# Board_roomba_final.net
KiCad netlist of a schematic drawn in EAGLE
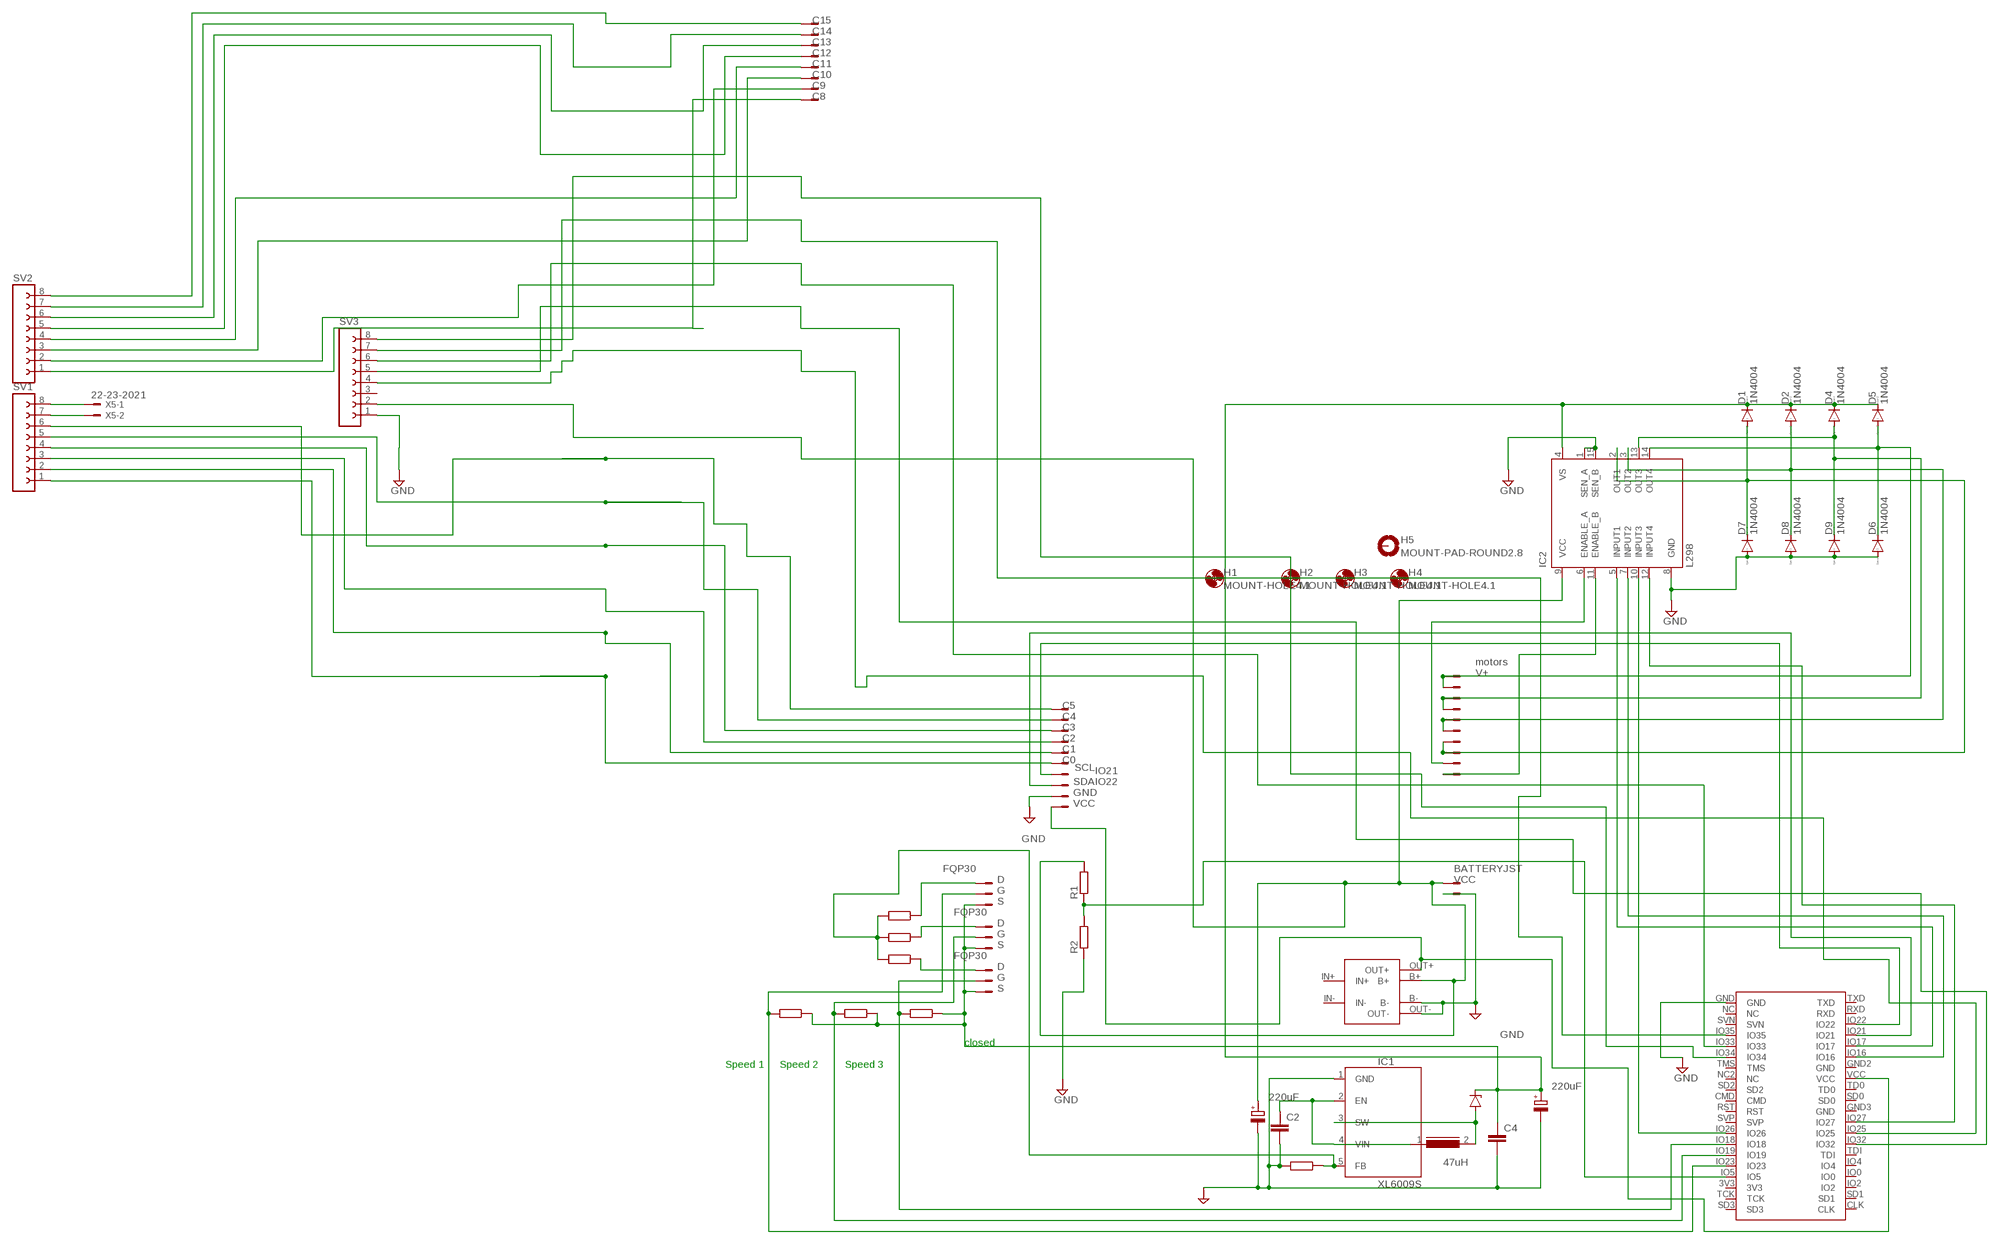
[diagram p0: schematic, sheet 1]

(export (version "E")
  (design (tool "Eeschema 10.0.6"))
  (components
    (comp (ref "C1")
      (value "CPOL-EUE2.5-7")
      (footprint "eagle-import:E2,5-7")
      (fields (field (name "SPICEPREFIX") "C") (field (name "SPICEPREFIX_1") "220uF"))
      (libsource (lib "eagle-import") (part "CPOL-EUE2.5-7"))
    )
    (comp (ref "C2")
      (value "C2,5-3")
      (footprint "eagle-import:C2.5-3")
      (libsource (lib "eagle-import") (part "C2,5-3"))
    )
    (comp (ref "C3")
      (value "CPOL-EUE2.5-7")
      (footprint "eagle-import:E2,5-7")
      (fields (field (name "SPICEPREFIX") "C") (field (name "SPICEPREFIX_1") "220uF"))
      (libsource (lib "eagle-import") (part "CPOL-EUE2.5-7"))
    )
    (comp (ref "C4")
      (value "C2,5-3")
      (footprint "eagle-import:C2.5-3")
      (libsource (lib "eagle-import") (part "C2,5-3"))
    )
    (comp (ref "D1")
      (value "1N4004")
      (footprint "eagle-import:DO41-10")
      (libsource (lib "eagle-import") (part "1N4004"))
    )
    (comp (ref "D2")
      (value "1N4004")
      (footprint "eagle-import:DO41-10")
      (libsource (lib "eagle-import") (part "1N4004"))
    )
    (comp (ref "D3")
      (value "1N4728")
      (footprint "eagle-import:DO41Z10")
      (libsource (lib "eagle-import") (part "1N4728"))
    )
    (comp (ref "D4")
      (value "1N4004")
      (footprint "eagle-import:DO41-10")
      (libsource (lib "eagle-import") (part "1N4004"))
    )
    (comp (ref "D5")
      (value "1N4004")
      (footprint "eagle-import:DO41-10")
      (libsource (lib "eagle-import") (part "1N4004"))
    )
    (comp (ref "D6")
      (value "1N4004")
      (footprint "eagle-import:DO41-10")
      (libsource (lib "eagle-import") (part "1N4004"))
    )
    (comp (ref "D7")
      (value "1N4004")
      (footprint "eagle-import:DO41-10")
      (libsource (lib "eagle-import") (part "1N4004"))
    )
    (comp (ref "D8")
      (value "1N4004")
      (footprint "eagle-import:DO41-10")
      (libsource (lib "eagle-import") (part "1N4004"))
    )
    (comp (ref "D9")
      (value "1N4004")
      (footprint "eagle-import:DO41-10")
      (libsource (lib "eagle-import") (part "1N4004"))
    )
    (comp (ref "H1")
      (value "MOUNT-HOLE4.1")
      (footprint "eagle-import:4,1")
      (libsource (lib "eagle-import") (part "MOUNT-HOLE4.1"))
    )
    (comp (ref "H2")
      (value "MOUNT-HOLE4.1")
      (footprint "eagle-import:4,1")
      (libsource (lib "eagle-import") (part "MOUNT-HOLE4.1"))
    )
    (comp (ref "H3")
      (value "MOUNT-HOLE4.1")
      (footprint "eagle-import:4,1")
      (libsource (lib "eagle-import") (part "MOUNT-HOLE4.1"))
    )
    (comp (ref "H4")
      (value "MOUNT-HOLE4.1")
      (footprint "eagle-import:4,1")
      (libsource (lib "eagle-import") (part "MOUNT-HOLE4.1"))
    )
    (comp (ref "H5")
      (value "MOUNT-PAD-ROUND2.8")
      (footprint "eagle-import:2,8-PAD")
      (libsource (lib "eagle-import") (part "MOUNT-PAD-ROUND2.8"))
    )
    (comp (ref "IC1")
      (value "XL6009S")
      (footprint "eagle-import:TO263-5")
      (libsource (lib "eagle-import") (part "XL6009S"))
    )
    (comp (ref "IC2")
      (value "L298")
      (footprint "eagle-import:MULTIWATT-15")
      (fields (field (name "MPN") "L298N"))
      (libsource (lib "eagle-import") (part "L298"))
    )
    (comp (ref "L1")
      (value "DR127")
      (footprint "eagle-import:DR127")
      (fields (field (name "47") "47uH"))
      (libsource (lib "eagle-import") (part "DR127"))
    )
    (comp (ref "R1")
      (value "R-EU_0207/10")
      (footprint "eagle-import:0207_10")
      (libsource (lib "eagle-import") (part "R-EU_0207/10"))
    )
    (comp (ref "R2")
      (value "R-EU_0207/10")
      (footprint "eagle-import:0207_10")
      (libsource (lib "eagle-import") (part "R-EU_0207/10"))
    )
    (comp (ref "R4")
      (value "R-EU_0207/10")
      (footprint "eagle-import:0207_10")
      (libsource (lib "eagle-import") (part "R-EU_0207/10"))
    )
    (comp (ref "R5")
      (value "R-EU_0207/10")
      (footprint "eagle-import:0207_10")
      (libsource (lib "eagle-import") (part "R-EU_0207/10"))
    )
    (comp (ref "R6")
      (value "R-EU_0207/10")
      (footprint "eagle-import:0207_10")
      (libsource (lib "eagle-import") (part "R-EU_0207/10"))
    )
    (comp (ref "R7")
      (value "R-EU_0207/10")
      (footprint "eagle-import:0207_10")
      (libsource (lib "eagle-import") (part "R-EU_0207/10"))
    )
    (comp (ref "R8")
      (value "R-EU_0207/10")
      (footprint "eagle-import:0207_10")
      (libsource (lib "eagle-import") (part "R-EU_0207/10"))
    )
    (comp (ref "R9")
      (value "R-EU_0207/10")
      (footprint "eagle-import:0207_10")
      (libsource (lib "eagle-import") (part "R-EU_0207/10"))
    )
    (comp (ref "R10")
      (value "R-EU_0207/10")
      (footprint "eagle-import:0207_10")
      (libsource (lib "eagle-import") (part "R-EU_0207/10"))
    )
    (comp (ref "SV1")
      (value "FE08W")
      (footprint "eagle-import:FE08W")
      (libsource (lib "eagle-import") (part "FE08W"))
    )
    (comp (ref "SV2")
      (value "FE08W")
      (footprint "eagle-import:FE08W")
      (libsource (lib "eagle-import") (part "FE08W"))
    )
    (comp (ref "SV3")
      (value "FE08W")
      (footprint "eagle-import:FE08W")
      (libsource (lib "eagle-import") (part "FE08W"))
    )
    (comp (ref "U$1")
      (value "TP4056")
      (footprint "eagle-import:TP4056")
      (libsource (lib "eagle-import") (part "TP4056"))
    )
    (comp (ref "U$2")
      (value "MH-ET_ESP32_D1_MINI")
      (footprint "eagle-import:MH-ET_ESP32_D1_MINI")
      (libsource (lib "eagle-import") (part "MH-ET_ESP32_D1_MINI"))
    )
    (comp (ref "X1")
      (value "22-23-2101")
      (footprint "eagle-import:22-23-2101")
      (fields
        (field (name "MF") "MOLEX")
        (field (name "GROUND") "GND")
        (field (name "IO21") "IO21")
        (field (name "IO22") "IO22")
        (field (name "SCL") "SCL")
        (field (name "VCC") "VCC")
      )
      (libsource (lib "eagle-import") (part "22-23-2101"))
    )
    (comp (ref "X2")
      (value "22-23-2031")
      (footprint "eagle-import:22-23-2031")
      (fields (field (name "MF") "MOLEX"))
      (libsource (lib "eagle-import") (part "22-23-2031"))
    )
    (comp (ref "X3")
      (value "22-23-2031")
      (footprint "eagle-import:22-23-2031")
      (fields (field (name "MF") "MOLEX"))
      (libsource (lib "eagle-import") (part "22-23-2031"))
    )
    (comp (ref "X4")
      (value "22-23-2101")
      (footprint "eagle-import:22-23-2101")
      (fields
        (field (name "MF") "MOLEX")
        (field (name "9V") "V+")
        (field (name "MPN") "22-23-2101")
        (field (name "MPN_1") "motors")
      )
      (libsource (lib "eagle-import") (part "22-23-2101"))
    )
    (comp (ref "X5")
      (value "22-23-2021")
      (footprint "eagle-import:22-23-2021")
      (fields (field (name "MF") "MOLEX"))
      (libsource (lib "eagle-import") (part "22-23-2021"))
    )
    (comp (ref "X6")
      (value "22-23-2081")
      (footprint "eagle-import:22-23-2081")
      (fields (field (name "MF") "MOLEX"))
      (libsource (lib "eagle-import") (part "22-23-2081"))
    )
    (comp (ref "X7")
      (value "22-23-2021")
      (footprint "eagle-import:22-23-2021")
      (fields (field (name "MF") "MOLEX"))
      (libsource (lib "eagle-import") (part "22-23-2021"))
    )
    (comp (ref "X9")
      (value "22-23-2031")
      (footprint "eagle-import:22-23-2031")
      (fields (field (name "MF") "MOLEX"))
      (libsource (lib "eagle-import") (part "22-23-2031"))
    )
  )
  (nets
    (net (code "1") (name "GND") (class "Default")
      (node (ref "C1") (pin "-") (pinfunction "-_-") (pintype "passive"))
      (node (ref "C2") (pin "2") (pinfunction "2_2") (pintype "passive"))
      (node (ref "C3") (pin "-") (pinfunction "-_-") (pintype "passive"))
      (node (ref "C4") (pin "2") (pinfunction "2_2") (pintype "passive"))
      (node (ref "D6") (pin "A") (pinfunction "A_A") (pintype "passive"))
      (node (ref "D7") (pin "A") (pinfunction "A_A") (pintype "passive"))
      (node (ref "D8") (pin "A") (pinfunction "A_A") (pintype "passive"))
      (node (ref "D9") (pin "A") (pinfunction "A_A") (pintype "passive"))
      (node (ref "IC1") (pin "1") (pinfunction "GND_1") (pintype "input"))
      (node (ref "IC2") (pin "1") (pinfunction "SEN_A_1") (pintype "input"))
      (node (ref "IC2") (pin "15") (pinfunction "SEN_B_15") (pintype "input"))
      (node (ref "IC2") (pin "8") (pinfunction "GND_8") (pintype "power_in"))
      (node (ref "R2") (pin "1") (pinfunction "1_1") (pintype "passive"))
      (node (ref "R4") (pin "2") (pinfunction "2_2") (pintype "passive"))
      (node (ref "SV3") (pin "1") (pinfunction "1_1") (pintype "passive"))
      (node (ref "U$1") (pin "B-") (pinfunction "B-_B-") (pintype "bidirectional"))
      (node (ref "U$1") (pin "OUT-") (pinfunction "OUT-_OUT-") (pintype "bidirectional"))
      (node (ref "U$2") (pin "GND") (pinfunction "GND_GND") (pintype "bidirectional"))
      (node (ref "X1") (pin "9") (pinfunction "S_9") (pintype "passive"))
      (node (ref "X7") (pin "2") (pinfunction "S_2") (pintype "passive"))
    )
    (net (code "2") (name "Net-(IC1-EN)") (class "Default")
      (node (ref "C2") (pin "1") (pinfunction "1_1") (pintype "passive"))
      (node (ref "IC1") (pin "2") (pinfunction "EN_2") (pintype "input"))
      (node (ref "IC1") (pin "4") (pinfunction "VIN_4") (pintype "power_in"))
      (node (ref "L1") (pin "1") (pinfunction "1_1") (pintype "passive"))
    )
    (net (code "3") (name "Net-(IC1-FB)") (class "Default")
      (node (ref "IC1") (pin "5") (pinfunction "FB_5") (pintype "output"))
      (node (ref "R4") (pin "1") (pinfunction "1_1") (pintype "passive"))
      (node (ref "R5") (pin "2") (pinfunction "2_2") (pintype "passive"))
      (node (ref "R6") (pin "2") (pinfunction "2_2") (pintype "passive"))
      (node (ref "R7") (pin "2") (pinfunction "2_2") (pintype "passive"))
    )
    (net (code "4") (name "Net-(IC1-SW)") (class "Default")
      (node (ref "D3") (pin "A") (pinfunction "A_A") (pintype "passive"))
      (node (ref "IC1") (pin "3") (pinfunction "SW_3") (pintype "power_in"))
      (node (ref "L1") (pin "2") (pinfunction "2_2") (pintype "passive"))
    )
    (net (code "5") (name "Net-(IC2-ENABLE_A)") (class "Default")
      (node (ref "IC2") (pin "6") (pinfunction "ENABLE_A_6") (pintype "input"))
      (node (ref "X4") (pin "9") (pinfunction "S_9") (pintype "passive"))
    )
    (net (code "6") (name "Net-(IC2-ENABLE_B)") (class "Default")
      (node (ref "IC2") (pin "11") (pinfunction "ENABLE_B_11") (pintype "input"))
      (node (ref "X4") (pin "10") (pinfunction "S_10") (pintype "passive"))
    )
    (net (code "7") (name "Net-(IC2-INPUT1)") (class "Default")
      (node (ref "IC2") (pin "5") (pinfunction "INPUT1_5") (pintype "input"))
      (node (ref "U$2") (pin "IO17") (pinfunction "IO17_IO17") (pintype "bidirectional"))
    )
    (net (code "8") (name "Net-(IC2-INPUT2)") (class "Default")
      (node (ref "IC2") (pin "7") (pinfunction "INPUT2_7") (pintype "input"))
      (node (ref "U$2") (pin "IO16") (pinfunction "IO16_IO16") (pintype "bidirectional"))
    )
    (net (code "9") (name "Net-(IC2-INPUT3)") (class "Default")
      (node (ref "IC2") (pin "10") (pinfunction "INPUT3_10") (pintype "input"))
      (node (ref "U$2") (pin "IO26") (pinfunction "IO26_IO26") (pintype "bidirectional"))
    )
    (net (code "10") (name "Net-(IC2-INPUT4)") (class "Default")
      (node (ref "IC2") (pin "12") (pinfunction "INPUT4_12") (pintype "input"))
      (node (ref "U$2") (pin "IO27") (pinfunction "IO27_IO27") (pintype "bidirectional"))
    )
    (net (code "11") (name "Net-(IC2-OUT1)") (class "Default")
      (node (ref "D1") (pin "A") (pinfunction "A_A") (pintype "passive"))
      (node (ref "D7") (pin "C") (pinfunction "C_C") (pintype "passive"))
      (node (ref "IC2") (pin "2") (pinfunction "OUT1_2") (pintype "output"))
      (node (ref "X4") (pin "7") (pinfunction "S_7") (pintype "passive"))
      (node (ref "X4") (pin "8") (pinfunction "S_8") (pintype "passive"))
    )
    (net (code "12") (name "Net-(IC2-OUT2)") (class "Default")
      (node (ref "D2") (pin "A") (pinfunction "A_A") (pintype "passive"))
      (node (ref "D8") (pin "C") (pinfunction "C_C") (pintype "passive"))
      (node (ref "IC2") (pin "3") (pinfunction "OUT2_3") (pintype "output"))
      (node (ref "X4") (pin "5") (pinfunction "S_5") (pintype "passive"))
      (node (ref "X4") (pin "6") (pinfunction "S_6") (pintype "passive"))
    )
    (net (code "13") (name "Net-(IC2-OUT3)") (class "Default")
      (node (ref "D4") (pin "A") (pinfunction "A_A") (pintype "passive"))
      (node (ref "D9") (pin "C") (pinfunction "C_C") (pintype "passive"))
      (node (ref "IC2") (pin "13") (pinfunction "OUT3_13") (pintype "output"))
      (node (ref "X4") (pin "3") (pinfunction "S_3") (pintype "passive"))
      (node (ref "X4") (pin "4") (pinfunction "S_4") (pintype "passive"))
    )
    (net (code "14") (name "Net-(IC2-OUT4)") (class "Default")
      (node (ref "D5") (pin "A") (pinfunction "A_A") (pintype "passive"))
      (node (ref "D6") (pin "C") (pinfunction "C_C") (pintype "passive"))
      (node (ref "IC2") (pin "14") (pinfunction "OUT4_14") (pintype "output"))
      (node (ref "X4") (pin "1") (pinfunction "S_1") (pintype "passive"))
      (node (ref "X4") (pin "2") (pinfunction "S_2") (pintype "passive"))
    )
    (net (code "15") (name "Net-(IC2-VCC)") (class "Default")
      (node (ref "C1") (pin "+") (pinfunction "+_+") (pintype "passive"))
      (node (ref "IC2") (pin "9") (pinfunction "VCC_9") (pintype "power_in"))
      (node (ref "R1") (pin "2") (pinfunction "2_2") (pintype "passive"))
      (node (ref "SV3") (pin "2") (pinfunction "2_2") (pintype "passive"))
      (node (ref "U$1") (pin "B+") (pinfunction "B+_B+") (pintype "bidirectional"))
      (node (ref "X7") (pin "1") (pinfunction "S_1") (pintype "passive"))
    )
    (net (code "16") (name "Net-(IC2-VS)") (class "Default")
      (node (ref "C3") (pin "+") (pinfunction "+_+") (pintype "passive"))
      (node (ref "C4") (pin "1") (pinfunction "1_1") (pintype "passive"))
      (node (ref "D1") (pin "C") (pinfunction "C_C") (pintype "passive"))
      (node (ref "D2") (pin "C") (pinfunction "C_C") (pintype "passive"))
      (node (ref "D3") (pin "C") (pinfunction "C_C") (pintype "passive"))
      (node (ref "D4") (pin "C") (pinfunction "C_C") (pintype "passive"))
      (node (ref "D5") (pin "C") (pinfunction "C_C") (pintype "passive"))
      (node (ref "IC2") (pin "4") (pinfunction "VS_4") (pintype "power_in"))
      (node (ref "R10") (pin "1") (pinfunction "1_1") (pintype "passive"))
      (node (ref "R8") (pin "1") (pinfunction "1_1") (pintype "passive"))
      (node (ref "R9") (pin "1") (pinfunction "1_1") (pintype "passive"))
      (node (ref "X2") (pin "3") (pinfunction "S_3") (pintype "passive"))
      (node (ref "X3") (pin "3") (pinfunction "S_3") (pintype "passive"))
      (node (ref "X9") (pin "3") (pinfunction "S_3") (pintype "passive"))
    )
    (net (code "17") (name "Net-(R1-Pad1)") (class "Default")
      (node (ref "R1") (pin "1") (pinfunction "1_1") (pintype "passive"))
      (node (ref "R2") (pin "2") (pinfunction "2_2") (pintype "passive"))
      (node (ref "U$2") (pin "IO5") (pinfunction "IO5_IO5") (pintype "bidirectional"))
    )
    (net (code "18") (name "Net-(SV3-Pad4)") (class "Default")
      (node (ref "SV3") (pin "4") (pinfunction "4_4") (pintype "passive"))
      (node (ref "U$2") (pin "IO25") (pinfunction "IO25_IO25") (pintype "bidirectional"))
    )
    (net (code "19") (name "Net-(SV3-Pad5)") (class "Default")
      (node (ref "SV3") (pin "5") (pinfunction "5_5") (pintype "passive"))
      (node (ref "U$2") (pin "IO32") (pinfunction "IO32_IO32") (pintype "bidirectional"))
    )
    (net (code "20") (name "Net-(SV3-Pad6)") (class "Default")
      (node (ref "SV3") (pin "6") (pinfunction "6_6") (pintype "passive"))
      (node (ref "U$2") (pin "IO33") (pinfunction "IO33_IO33") (pintype "bidirectional"))
    )
    (net (code "21") (name "Net-(SV3-Pad7)") (class "Default")
      (node (ref "SV3") (pin "7") (pinfunction "7_7") (pintype "passive"))
      (node (ref "U$2") (pin "IO35") (pinfunction "IO35_IO35") (pintype "bidirectional"))
    )
    (net (code "22") (name "Net-(SV3-Pad8)") (class "Default")
      (node (ref "SV3") (pin "8") (pinfunction "8_8") (pintype "passive"))
      (node (ref "U$2") (pin "IO34") (pinfunction "IO34_IO34") (pintype "bidirectional"))
    )
    (net (code "23") (name "Net-(X1A-S)") (class "Default")
      (node (ref "SV1") (pin "6") (pinfunction "6_6") (pintype "passive"))
      (node (ref "X1") (pin "1") (pinfunction "S_1") (pintype "passive"))
    )
    (net (code "24") (name "Net-(X1B-S)") (class "Default")
      (node (ref "U$1") (pin "OUT+") (pinfunction "OUT+_OUT+") (pintype "bidirectional"))
      (node (ref "U$2") (pin "VCC") (pinfunction "VCC_VCC") (pintype "bidirectional"))
      (node (ref "X1") (pin "10") (pinfunction "S_10") (pintype "passive"))
    )
    (net (code "25") (name "Net-(X1C-S)") (class "Default")
      (node (ref "SV1") (pin "5") (pinfunction "5_5") (pintype "passive"))
      (node (ref "X1") (pin "2") (pinfunction "S_2") (pintype "passive"))
    )
    (net (code "26") (name "Net-(X1D-S)") (class "Default")
      (node (ref "SV1") (pin "4") (pinfunction "4_4") (pintype "passive"))
      (node (ref "X1") (pin "3") (pinfunction "S_3") (pintype "passive"))
    )
    (net (code "27") (name "Net-(X1E-S)") (class "Default")
      (node (ref "SV1") (pin "3") (pinfunction "3_3") (pintype "passive"))
      (node (ref "X1") (pin "4") (pinfunction "S_4") (pintype "passive"))
    )
    (net (code "28") (name "Net-(X1F-S)") (class "Default")
      (node (ref "SV1") (pin "2") (pinfunction "2_2") (pintype "passive"))
      (node (ref "X1") (pin "5") (pinfunction "S_5") (pintype "passive"))
    )
    (net (code "29") (name "Net-(X1G-S)") (class "Default")
      (node (ref "SV1") (pin "1") (pinfunction "1_1") (pintype "passive"))
      (node (ref "X1") (pin "6") (pinfunction "S_6") (pintype "passive"))
    )
    (net (code "30") (name "Net-(X1H-S)") (class "Default")
      (node (ref "U$2") (pin "IO22") (pinfunction "IO22_IO22") (pintype "bidirectional"))
      (node (ref "X1") (pin "7") (pinfunction "S_7") (pintype "passive"))
    )
    (net (code "31") (name "Net-(X1I-S)") (class "Default")
      (node (ref "U$2") (pin "IO21") (pinfunction "IO21_IO21") (pintype "bidirectional"))
      (node (ref "X1") (pin "8") (pinfunction "S_8") (pintype "passive"))
    )
    (net (code "32") (name "Net-(X2A-S)") (class "Default")
      (node (ref "R6") (pin "1") (pinfunction "1_1") (pintype "passive"))
      (node (ref "X2") (pin "1") (pinfunction "S_1") (pintype "passive"))
    )
    (net (code "33") (name "Net-(X2B-S)") (class "Default")
      (node (ref "R9") (pin "2") (pinfunction "2_2") (pintype "passive"))
      (node (ref "U$2") (pin "IO19") (pinfunction "IO19_IO19") (pintype "bidirectional"))
      (node (ref "X2") (pin "2") (pinfunction "S_2") (pintype "passive"))
    )
    (net (code "34") (name "Net-(X3A-S)") (class "Default")
      (node (ref "R7") (pin "1") (pinfunction "1_1") (pintype "passive"))
      (node (ref "X3") (pin "1") (pinfunction "S_1") (pintype "passive"))
    )
    (net (code "35") (name "Net-(X3B-S)") (class "Default")
      (node (ref "R8") (pin "2") (pinfunction "2_2") (pintype "passive"))
      (node (ref "U$2") (pin "IO18") (pinfunction "IO18_IO18") (pintype "bidirectional"))
      (node (ref "X3") (pin "2") (pinfunction "S_2") (pintype "passive"))
    )
    (net (code "36") (name "Net-(X5A-S)") (class "Default")
      (node (ref "SV1") (pin "8") (pinfunction "8_8") (pintype "passive"))
      (node (ref "X5") (pin "1") (pinfunction "S_1") (pintype "passive"))
    )
    (net (code "37") (name "Net-(X5B-S)") (class "Default")
      (node (ref "SV1") (pin "7") (pinfunction "7_7") (pintype "passive"))
      (node (ref "X5") (pin "2") (pinfunction "S_2") (pintype "passive"))
    )
    (net (code "38") (name "Net-(X6A-S)") (class "Default")
      (node (ref "SV2") (pin "8") (pinfunction "8_8") (pintype "passive"))
      (node (ref "X6") (pin "1") (pinfunction "S_1") (pintype "passive"))
    )
    (net (code "39") (name "Net-(X6B-S)") (class "Default")
      (node (ref "SV2") (pin "7") (pinfunction "7_7") (pintype "passive"))
      (node (ref "X6") (pin "2") (pinfunction "S_2") (pintype "passive"))
    )
    (net (code "40") (name "Net-(X6C-S)") (class "Default")
      (node (ref "SV2") (pin "6") (pinfunction "6_6") (pintype "passive"))
      (node (ref "X6") (pin "3") (pinfunction "S_3") (pintype "passive"))
    )
    (net (code "41") (name "Net-(X6D-S)") (class "Default")
      (node (ref "SV2") (pin "5") (pinfunction "5_5") (pintype "passive"))
      (node (ref "X6") (pin "4") (pinfunction "S_4") (pintype "passive"))
    )
    (net (code "42") (name "Net-(X6E-S)") (class "Default")
      (node (ref "SV2") (pin "4") (pinfunction "4_4") (pintype "passive"))
      (node (ref "X6") (pin "5") (pinfunction "S_5") (pintype "passive"))
    )
    (net (code "43") (name "Net-(X6F-S)") (class "Default")
      (node (ref "SV2") (pin "3") (pinfunction "3_3") (pintype "passive"))
      (node (ref "X6") (pin "6") (pinfunction "S_6") (pintype "passive"))
    )
    (net (code "44") (name "Net-(X6G-S)") (class "Default")
      (node (ref "SV2") (pin "2") (pinfunction "2_2") (pintype "passive"))
      (node (ref "X6") (pin "7") (pinfunction "S_7") (pintype "passive"))
    )
    (net (code "45") (name "Net-(X6H-S)") (class "Default")
      (node (ref "SV2") (pin "1") (pinfunction "1_1") (pintype "passive"))
      (node (ref "X6") (pin "8") (pinfunction "S_8") (pintype "passive"))
    )
    (net (code "46") (name "Net-(X9A-S)") (class "Default")
      (node (ref "R5") (pin "1") (pinfunction "1_1") (pintype "passive"))
      (node (ref "X9") (pin "1") (pinfunction "S_1") (pintype "passive"))
    )
    (net (code "47") (name "Net-(X9B-S)") (class "Default")
      (node (ref "R10") (pin "2") (pinfunction "2_2") (pintype "passive"))
      (node (ref "U$2") (pin "IO23") (pinfunction "IO23_IO23") (pintype "bidirectional"))
      (node (ref "X9") (pin "2") (pinfunction "S_2") (pintype "passive"))
    )
    (net (code "48") (name "unconnected-(H5-MOUNT-PadB2,8)") (class "Default")
      (node (ref "H5") (pin "B2,8") (pinfunction "MOUNT_B2,8") (pintype "passive"))
    )
    (net (code "49") (name "unconnected-(SV3-Pad3)") (class "Default")
      (node (ref "SV3") (pin "3") (pinfunction "3_3") (pintype "passive"))
    )
    (net (code "50") (name "unconnected-(U$1-PadIN+)") (class "Default")
      (node (ref "U$1") (pin "IN+") (pinfunction "IN+_IN+") (pintype "bidirectional"))
    )
    (net (code "51") (name "unconnected-(U$1-PadIN-)") (class "Default")
      (node (ref "U$1") (pin "IN-") (pinfunction "IN-_IN-") (pintype "bidirectional"))
    )
    (net (code "52") (name "unconnected-(U$2-GND-PadGND2)") (class "Default")
      (node (ref "U$2") (pin "GND2") (pinfunction "GND_GND2") (pintype "bidirectional"))
    )
    (net (code "53") (name "unconnected-(U$2-GND-PadGND3)") (class "Default")
      (node (ref "U$2") (pin "GND3") (pinfunction "GND_GND3") (pintype "bidirectional"))
    )
    (net (code "54") (name "unconnected-(U$2-NC-PadNC2)") (class "Default")
      (node (ref "U$2") (pin "NC2") (pinfunction "NC_NC2") (pintype "bidirectional"))
    )
    (net (code "55") (name "unconnected-(U$2-Pad3V3)") (class "Default")
      (node (ref "U$2") (pin "3V3") (pinfunction "3V3_3V3") (pintype "bidirectional"))
    )
    (net (code "56") (name "unconnected-(U$2-PadCLK)") (class "Default")
      (node (ref "U$2") (pin "CLK") (pinfunction "CLK_CLK") (pintype "bidirectional"))
    )
    (net (code "57") (name "unconnected-(U$2-PadCMD)") (class "Default")
      (node (ref "U$2") (pin "CMD") (pinfunction "CMD_CMD") (pintype "bidirectional"))
    )
    (net (code "58") (name "unconnected-(U$2-PadIO0)") (class "Default")
      (node (ref "U$2") (pin "IO0") (pinfunction "IO0_IO0") (pintype "bidirectional"))
    )
    (net (code "59") (name "unconnected-(U$2-PadIO2)") (class "Default")
      (node (ref "U$2") (pin "IO2") (pinfunction "IO2_IO2") (pintype "bidirectional"))
    )
    (net (code "60") (name "unconnected-(U$2-PadIO4)") (class "Default")
      (node (ref "U$2") (pin "IO4") (pinfunction "IO4_IO4") (pintype "bidirectional"))
    )
    (net (code "61") (name "unconnected-(U$2-PadNC)") (class "Default")
      (node (ref "U$2") (pin "NC") (pinfunction "NC_NC") (pintype "bidirectional"))
    )
    (net (code "62") (name "unconnected-(U$2-PadRST)") (class "Default")
      (node (ref "U$2") (pin "RST") (pinfunction "RST_RST") (pintype "bidirectional"))
    )
    (net (code "63") (name "unconnected-(U$2-PadRXD)") (class "Default")
      (node (ref "U$2") (pin "RXD") (pinfunction "RXD_RXD") (pintype "bidirectional"))
    )
    (net (code "64") (name "unconnected-(U$2-PadSD0)") (class "Default")
      (node (ref "U$2") (pin "SD0") (pinfunction "SD0_SD0") (pintype "bidirectional"))
    )
    (net (code "65") (name "unconnected-(U$2-PadSD1)") (class "Default")
      (node (ref "U$2") (pin "SD1") (pinfunction "SD1_SD1") (pintype "bidirectional"))
    )
    (net (code "66") (name "unconnected-(U$2-PadSD2)") (class "Default")
      (node (ref "U$2") (pin "SD2") (pinfunction "SD2_SD2") (pintype "bidirectional"))
    )
    (net (code "67") (name "unconnected-(U$2-PadSD3)") (class "Default")
      (node (ref "U$2") (pin "SD3") (pinfunction "SD3_SD3") (pintype "bidirectional"))
    )
    (net (code "68") (name "unconnected-(U$2-PadSVN)") (class "Default")
      (node (ref "U$2") (pin "SVN") (pinfunction "SVN_SVN") (pintype "bidirectional"))
    )
    (net (code "69") (name "unconnected-(U$2-PadSVP)") (class "Default")
      (node (ref "U$2") (pin "SVP") (pinfunction "SVP_SVP") (pintype "bidirectional"))
    )
    (net (code "70") (name "unconnected-(U$2-PadTCK)") (class "Default")
      (node (ref "U$2") (pin "TCK") (pinfunction "TCK_TCK") (pintype "bidirectional"))
    )
    (net (code "71") (name "unconnected-(U$2-PadTD0)") (class "Default")
      (node (ref "U$2") (pin "TD0") (pinfunction "TD0_TD0") (pintype "bidirectional"))
    )
    (net (code "72") (name "unconnected-(U$2-PadTDI)") (class "Default")
      (node (ref "U$2") (pin "TDI") (pinfunction "TDI_TDI") (pintype "bidirectional"))
    )
    (net (code "73") (name "unconnected-(U$2-PadTMS)") (class "Default")
      (node (ref "U$2") (pin "TMS") (pinfunction "TMS_TMS") (pintype "bidirectional"))
    )
    (net (code "74") (name "unconnected-(U$2-PadTXD)") (class "Default")
      (node (ref "U$2") (pin "TXD") (pinfunction "TXD_TXD") (pintype "bidirectional"))
    )
  )
)
